# MCU_Schematic.net
KiCad netlist of a schematic drawn in Altium Designer
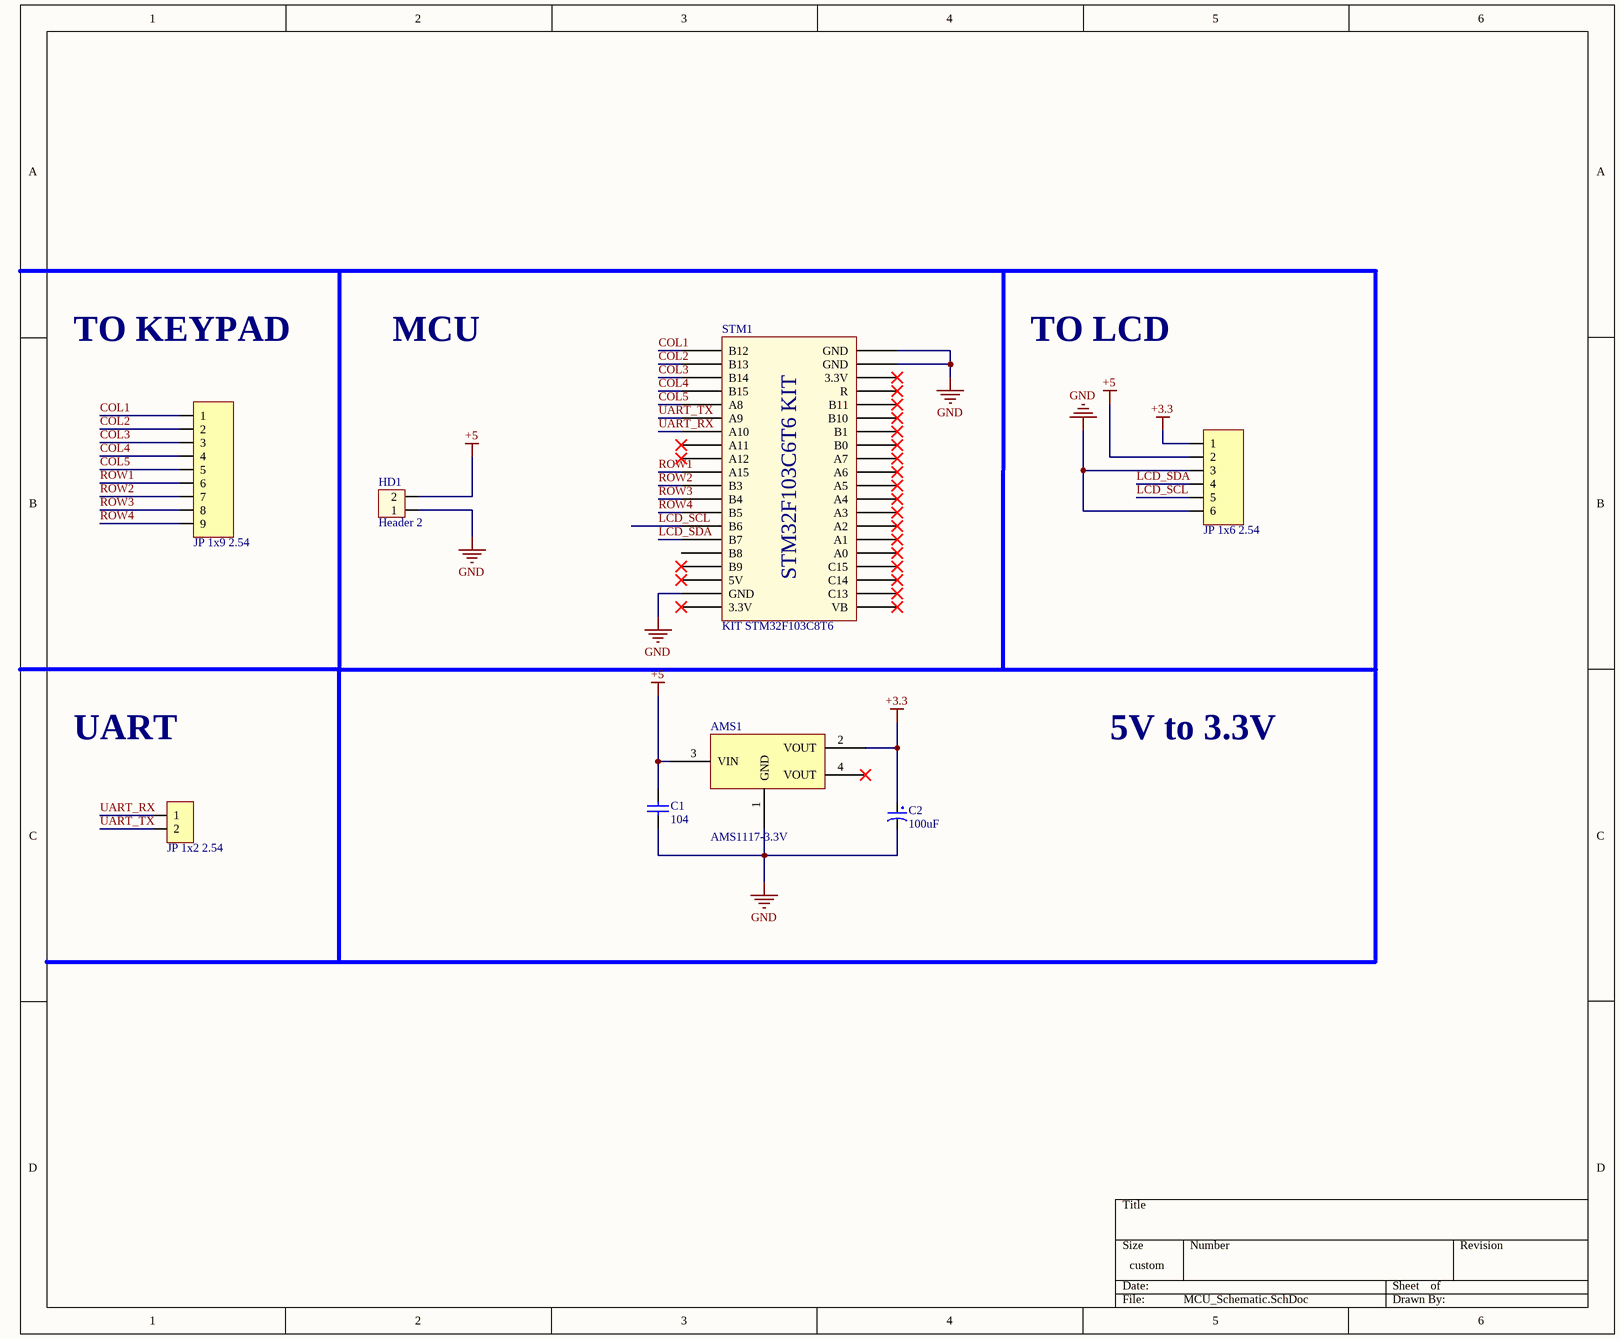
[diagram p0: MCU_Schematic.SchDoc]

(export (version "E")
  (design (tool "Eeschema 10.0.6"))
  (components
    (comp (ref "AMS1")
      (value "AMS1117-3.3V")
      (footprint "SOT223")
      (description "Dán")
      (libsource (lib "Altium_Lib_by_KhueNguyenCreator") (part "AMS1117 SMD"))
    )
    (comp (ref "C1")
      (value "104")
      (footprint "tu gom")
      (description "Cắm")
      (libsource (lib "Altium_Lib_by_KhueNguyenCreator") (part "Tu gom 104 50V"))
    )
    (comp (ref "C2")
      (value "100uF")
      (footprint "tu hoa 5mm")
      (description "Cắm")
      (libsource (lib "Altium_Lib_by_KhueNguyenCreator") (part "Tu Hoa 100uF 16V 5x7"))
    )
    (comp (ref "HD1")
      (value "Header 2")
      (footprint "HED2")
      (description "Header 2 (Green)")
      (libsource (lib "syhaunguyen") (part "Hed2"))
    )
    (comp (ref "JP2")
      (value "JP 1x9 2.54")
      (footprint "JP 1x9 DC")
      (description "Cắm")
      (libsource (lib "Altium_Lib_by_KhueNguyenCreator") (part "JP 1x9 2.54 Duc Cong"))
    )
    (comp (ref "JP3")
      (value "JP 1x6 2.54")
      (footprint "JP 1x6 DC")
      (description "Cắm")
      (libsource (lib "Altium_Lib_by_KhueNguyenCreator") (part "JP 1x6 2.54 Duc Cong"))
    )
    (comp (ref "JP4")
      (value "JP 1x2 2.54")
      (footprint "JP 1x2 DC")
      (description "Cắm")
      (libsource (lib "Altium_Lib_by_KhueNguyenCreator") (part "JP 1x2 2.54 Duc Cong"))
    )
    (comp (ref "STM1")
      (value "KIT STM32F103C8T6")
      (footprint "STM32F103 KIT")
      (description "KIT STM32F103C8T6 Bluepill")
      (libsource (lib "Altium_Lib_by_KhueNguyenCreator") (part "STM32f103 Bluepill"))
    )
  )
  (nets
    (net (code "1") (name "+3.3") (class "Default")
      (node (ref "AMS1") (pin "2") (pinfunction "VOUT_2") (pintype "passive"))
      (node (ref "C2") (pin "1") (pinfunction "1_1") (pintype "passive"))
      (node (ref "JP3") (pin "1") (pinfunction "1_1") (pintype "passive"))
    )
    (net (code "2") (name "+5") (class "Default")
      (node (ref "AMS1") (pin "3") (pinfunction "VIN_3") (pintype "passive"))
      (node (ref "C1") (pin "1") (pinfunction "1_1") (pintype "passive"))
      (node (ref "HD1") (pin "2") (pinfunction "2_2") (pintype "passive"))
      (node (ref "JP3") (pin "2") (pinfunction "2_2") (pintype "passive"))
    )
    (net (code "3") (name "/COL1") (class "Default")
      (node (ref "JP2") (pin "1") (pinfunction "1_1") (pintype "passive"))
      (node (ref "STM1") (pin "1") (pinfunction "B12_1") (pintype "passive"))
    )
    (net (code "4") (name "/COL2") (class "Default")
      (node (ref "JP2") (pin "2") (pinfunction "2_2") (pintype "passive"))
      (node (ref "STM1") (pin "2") (pinfunction "B13_2") (pintype "passive"))
    )
    (net (code "5") (name "/COL3") (class "Default")
      (node (ref "JP2") (pin "3") (pinfunction "3_3") (pintype "passive"))
      (node (ref "STM1") (pin "3") (pinfunction "B14_3") (pintype "passive"))
    )
    (net (code "6") (name "/COL4") (class "Default")
      (node (ref "JP2") (pin "4") (pinfunction "4_4") (pintype "passive"))
      (node (ref "STM1") (pin "4") (pinfunction "B15_4") (pintype "passive"))
    )
    (net (code "7") (name "/COL5") (class "Default")
      (node (ref "JP2") (pin "5") (pinfunction "5_5") (pintype "passive"))
      (node (ref "STM1") (pin "5") (pinfunction "A8_5") (pintype "passive"))
    )
    (net (code "8") (name "/LCD_SCL") (class "Default")
      (node (ref "JP3") (pin "5") (pinfunction "5_5") (pintype "passive"))
      (node (ref "STM1") (pin "14") (pinfunction "B6_14") (pintype "passive"))
    )
    (net (code "9") (name "/LCD_SDA") (class "Default")
      (node (ref "JP3") (pin "4") (pinfunction "4_4") (pintype "passive"))
      (node (ref "STM1") (pin "15") (pinfunction "B7_15") (pintype "passive"))
    )
    (net (code "10") (name "/ROW1") (class "Default")
      (node (ref "JP2") (pin "6") (pinfunction "6_6") (pintype "passive"))
      (node (ref "STM1") (pin "10") (pinfunction "A15_10") (pintype "passive"))
    )
    (net (code "11") (name "/ROW2") (class "Default")
      (node (ref "JP2") (pin "7") (pinfunction "7_7") (pintype "passive"))
      (node (ref "STM1") (pin "11") (pinfunction "B3_11") (pintype "passive"))
    )
    (net (code "12") (name "/ROW3") (class "Default")
      (node (ref "JP2") (pin "8") (pinfunction "8_8") (pintype "passive"))
      (node (ref "STM1") (pin "12") (pinfunction "B4_12") (pintype "passive"))
    )
    (net (code "13") (name "/ROW4") (class "Default")
      (node (ref "JP2") (pin "9") (pinfunction "9_9") (pintype "passive"))
      (node (ref "STM1") (pin "13") (pinfunction "B5_13") (pintype "passive"))
    )
    (net (code "14") (name "/UART_RX") (class "Default")
      (node (ref "JP4") (pin "1") (pinfunction "1_1") (pintype "passive"))
      (node (ref "STM1") (pin "7") (pinfunction "A10_7") (pintype "passive"))
    )
    (net (code "15") (name "/UART_TX") (class "Default")
      (node (ref "JP4") (pin "2") (pinfunction "2_2") (pintype "passive"))
      (node (ref "STM1") (pin "6") (pinfunction "A9_6") (pintype "passive"))
    )
    (net (code "16") (name "GND") (class "Default")
      (node (ref "AMS1") (pin "1") (pinfunction "GND_1") (pintype "passive"))
      (node (ref "C1") (pin "2") (pinfunction "2_2") (pintype "passive"))
      (node (ref "C2") (pin "2") (pinfunction "2_2") (pintype "passive"))
      (node (ref "HD1") (pin "1") (pinfunction "1_1") (pintype "passive"))
      (node (ref "JP3") (pin "3") (pinfunction "3_3") (pintype "passive"))
      (node (ref "JP3") (pin "6") (pinfunction "6_6") (pintype "passive"))
      (node (ref "STM1") (pin "19") (pinfunction "GND_19") (pintype "passive"))
      (node (ref "STM1") (pin "39") (pinfunction "GND_39") (pintype "passive"))
      (node (ref "STM1") (pin "40") (pinfunction "GND_40") (pintype "passive"))
    )
    (net (code "17") (name "unconnected-(AMS1-VOUT-Pad4)") (class "Default")
      (node (ref "AMS1") (pin "4") (pinfunction "VOUT_4") (pintype "passive+no_connect"))
    )
    (net (code "18") (name "unconnected-(STM1-3.3V-Pad20)") (class "Default")
      (node (ref "STM1") (pin "20") (pinfunction "3.3V_20") (pintype "passive+no_connect"))
    )
    (net (code "19") (name "unconnected-(STM1-3.3V-Pad38)") (class "Default")
      (node (ref "STM1") (pin "38") (pinfunction "3.3V_38") (pintype "passive+no_connect"))
    )
    (net (code "20") (name "unconnected-(STM1-5V-Pad18)") (class "Default")
      (node (ref "STM1") (pin "18") (pinfunction "5V_18") (pintype "passive+no_connect"))
    )
    (net (code "21") (name "unconnected-(STM1-A0-Pad25)") (class "Default")
      (node (ref "STM1") (pin "25") (pinfunction "A0_25") (pintype "passive+no_connect"))
    )
    (net (code "22") (name "unconnected-(STM1-A1-Pad26)") (class "Default")
      (node (ref "STM1") (pin "26") (pinfunction "A1_26") (pintype "passive+no_connect"))
    )
    (net (code "23") (name "unconnected-(STM1-A2-Pad27)") (class "Default")
      (node (ref "STM1") (pin "27") (pinfunction "A2_27") (pintype "passive+no_connect"))
    )
    (net (code "24") (name "unconnected-(STM1-A3-Pad28)") (class "Default")
      (node (ref "STM1") (pin "28") (pinfunction "A3_28") (pintype "passive+no_connect"))
    )
    (net (code "25") (name "unconnected-(STM1-A4-Pad29)") (class "Default")
      (node (ref "STM1") (pin "29") (pinfunction "A4_29") (pintype "passive+no_connect"))
    )
    (net (code "26") (name "unconnected-(STM1-A5-Pad30)") (class "Default")
      (node (ref "STM1") (pin "30") (pinfunction "A5_30") (pintype "passive+no_connect"))
    )
    (net (code "27") (name "unconnected-(STM1-A6-Pad31)") (class "Default")
      (node (ref "STM1") (pin "31") (pinfunction "A6_31") (pintype "passive+no_connect"))
    )
    (net (code "28") (name "unconnected-(STM1-A7-Pad32)") (class "Default")
      (node (ref "STM1") (pin "32") (pinfunction "A7_32") (pintype "passive+no_connect"))
    )
    (net (code "29") (name "unconnected-(STM1-A11-Pad8)") (class "Default")
      (node (ref "STM1") (pin "8") (pinfunction "A11_8") (pintype "passive+no_connect"))
    )
    (net (code "30") (name "unconnected-(STM1-A12-Pad9)") (class "Default")
      (node (ref "STM1") (pin "9") (pinfunction "A12_9") (pintype "passive+no_connect"))
    )
    (net (code "31") (name "unconnected-(STM1-B0-Pad33)") (class "Default")
      (node (ref "STM1") (pin "33") (pinfunction "B0_33") (pintype "passive+no_connect"))
    )
    (net (code "32") (name "unconnected-(STM1-B1-Pad34)") (class "Default")
      (node (ref "STM1") (pin "34") (pinfunction "B1_34") (pintype "passive+no_connect"))
    )
    (net (code "33") (name "unconnected-(STM1-B8-Pad16)") (class "Default")
      (node (ref "STM1") (pin "16") (pinfunction "B8_16") (pintype "passive"))
    )
    (net (code "34") (name "unconnected-(STM1-B9-Pad17)") (class "Default")
      (node (ref "STM1") (pin "17") (pinfunction "B9_17") (pintype "passive+no_connect"))
    )
    (net (code "35") (name "unconnected-(STM1-B10-Pad35)") (class "Default")
      (node (ref "STM1") (pin "35") (pinfunction "B10_35") (pintype "passive+no_connect"))
    )
    (net (code "36") (name "unconnected-(STM1-B11-Pad36)") (class "Default")
      (node (ref "STM1") (pin "36") (pinfunction "B11_36") (pintype "passive+no_connect"))
    )
    (net (code "37") (name "unconnected-(STM1-C13-Pad22)") (class "Default")
      (node (ref "STM1") (pin "22") (pinfunction "C13_22") (pintype "passive+no_connect"))
    )
    (net (code "38") (name "unconnected-(STM1-C14-Pad23)") (class "Default")
      (node (ref "STM1") (pin "23") (pinfunction "C14_23") (pintype "passive+no_connect"))
    )
    (net (code "39") (name "unconnected-(STM1-C15-Pad24)") (class "Default")
      (node (ref "STM1") (pin "24") (pinfunction "C15_24") (pintype "passive+no_connect"))
    )
    (net (code "40") (name "unconnected-(STM1-R-Pad37)") (class "Default")
      (node (ref "STM1") (pin "37") (pinfunction "R_37") (pintype "passive+no_connect"))
    )
    (net (code "41") (name "unconnected-(STM1-VB-Pad21)") (class "Default")
      (node (ref "STM1") (pin "21") (pinfunction "VB_21") (pintype "passive+no_connect"))
    )
  )
)
